# MVFD_I2C_Backpack.net
KiCad netlist of a schematic drawn in EAGLE
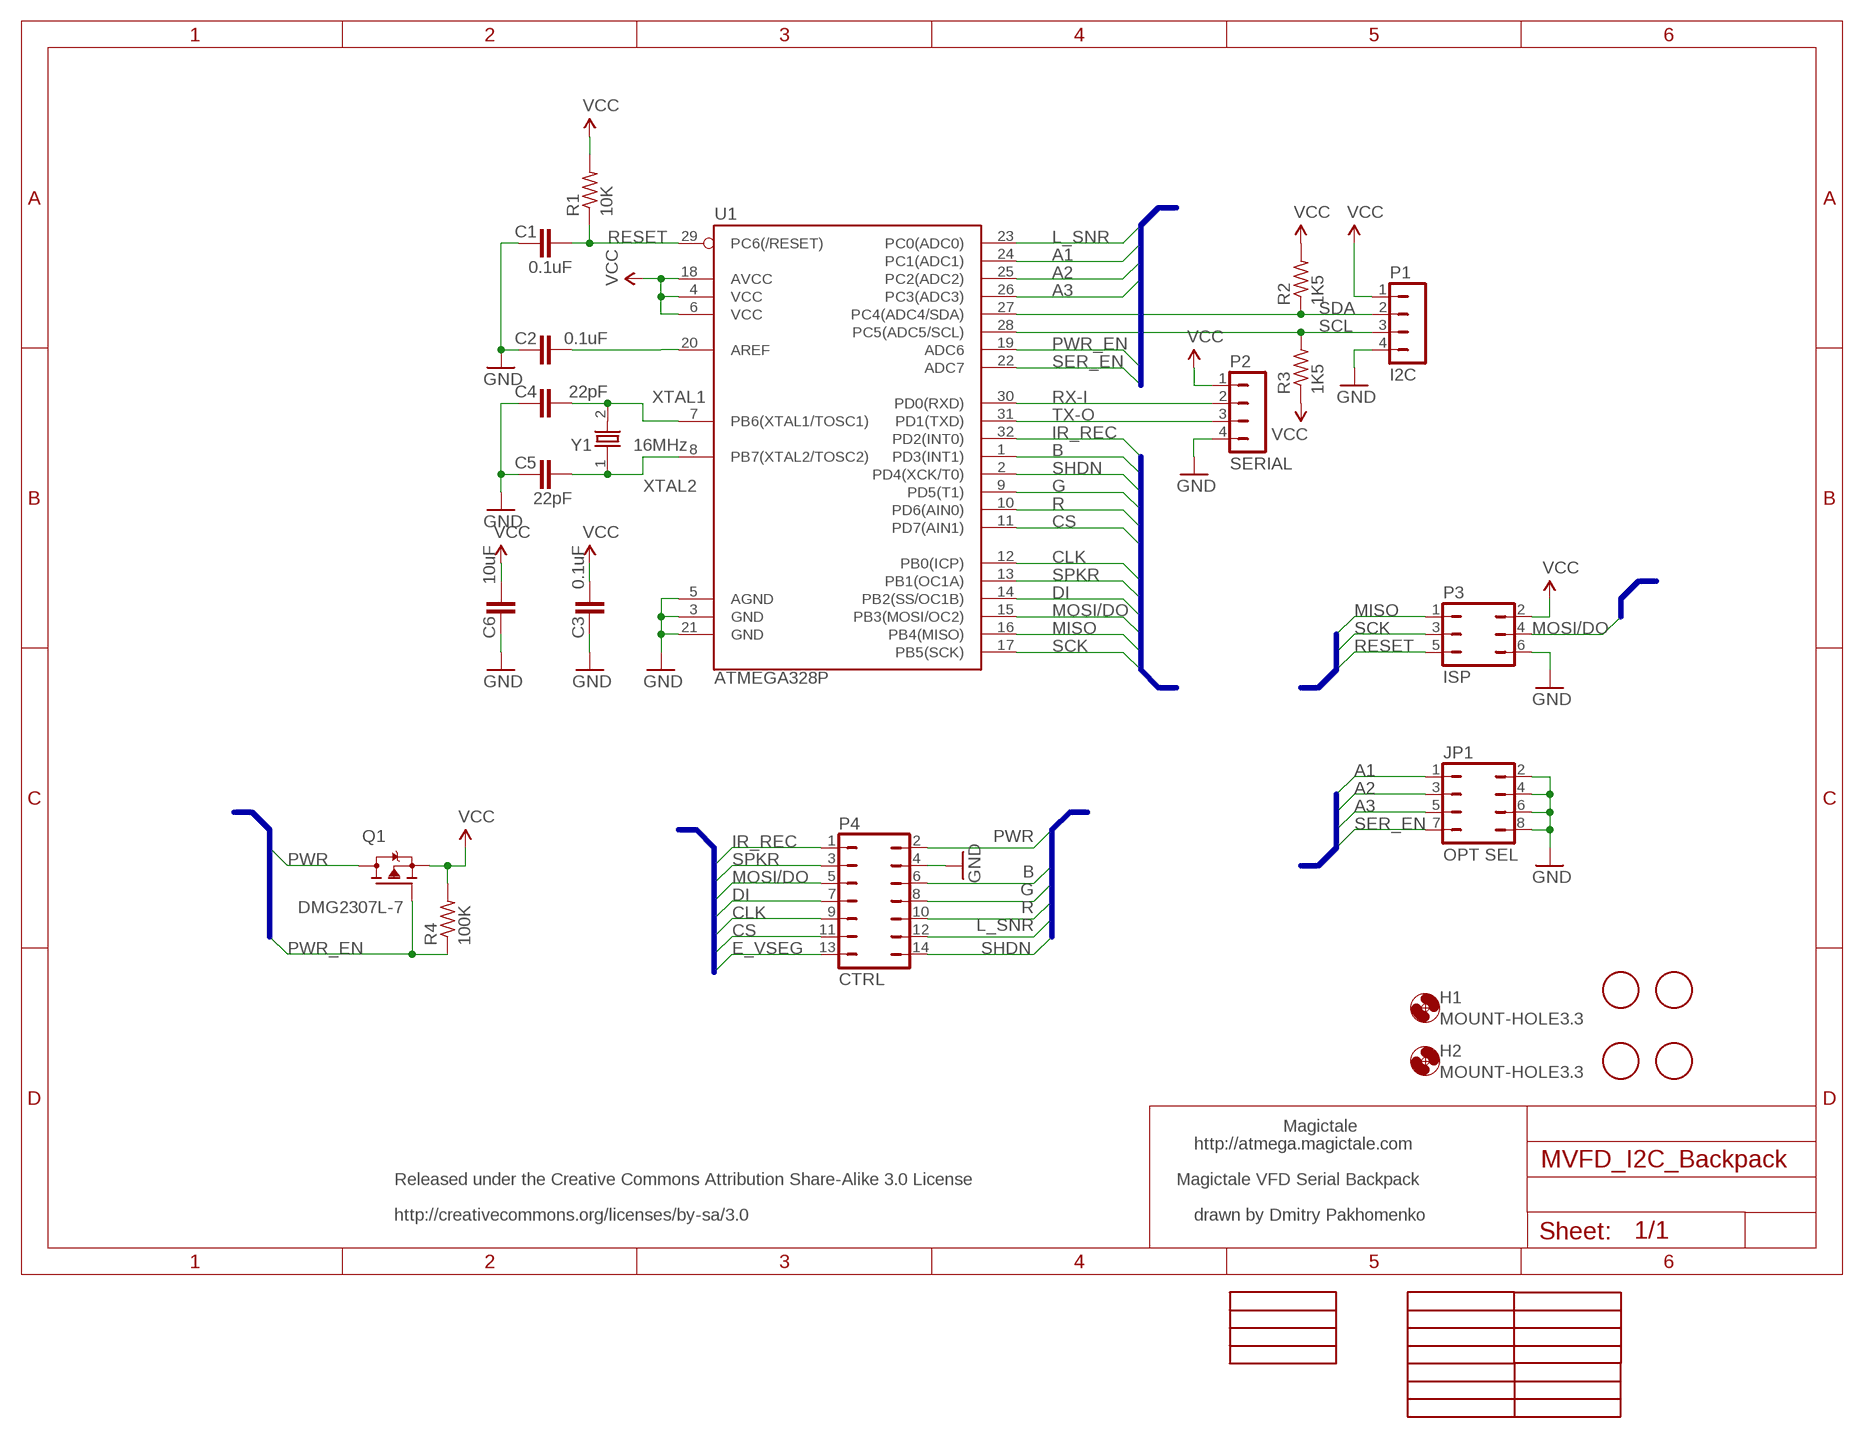
[diagram p0: schematic, sheet 1]

(export (version "E")
  (design (tool "Eeschema 10.0.6"))
  (components
    (comp (ref "C1")
      (value "0.1uF")
      (footprint "eagle-import:C1206")
      (libsource (lib "eagle-import") (part "CAPACITOR_NPOL-1206"))
    )
    (comp (ref "C2")
      (value "0.1uF")
      (footprint "eagle-import:C1206")
      (libsource (lib "eagle-import") (part "CAPACITOR_NPOL-1206"))
    )
    (comp (ref "C3")
      (value "0.1uF")
      (footprint "eagle-import:C1206")
      (libsource (lib "eagle-import") (part "CAPACITOR_NPOL-1206"))
    )
    (comp (ref "C4")
      (value "22pF")
      (footprint "eagle-import:C1206")
      (libsource (lib "eagle-import") (part "CAPACITOR_NPOL-1206"))
    )
    (comp (ref "C5")
      (value "22pF")
      (footprint "eagle-import:C1206")
      (libsource (lib "eagle-import") (part "CAPACITOR_NPOL-1206"))
    )
    (comp (ref "C6")
      (value "10uF")
      (footprint "eagle-import:C1206")
      (libsource (lib "eagle-import") (part "CAPACITOR_NPOL-1206"))
    )
    (comp (ref "FIDUTIAL1")
      (value "FIDUCIAL")
      (footprint "eagle-import:FIDUCIAL_1MM")
      (libsource (lib "eagle-import") (part "FIDUCIAL"))
    )
    (comp (ref "FIDUTIAL2")
      (value "FIDUCIAL")
      (footprint "eagle-import:FIDUCIAL_1MM")
      (libsource (lib "eagle-import") (part "FIDUCIAL"))
    )
    (comp (ref "FIDUTIAL3")
      (value "FIDUCIAL")
      (footprint "eagle-import:FIDUCIAL_1MM")
      (libsource (lib "eagle-import") (part "FIDUCIAL"))
    )
    (comp (ref "FIDUTIAL4")
      (value "FIDUCIAL")
      (footprint "eagle-import:FIDUCIAL_1MM")
      (libsource (lib "eagle-import") (part "FIDUCIAL"))
    )
    (comp (ref "H1")
      (value "MOUNT-HOLE3.3")
      (footprint "eagle-import:3,3")
      (libsource (lib "eagle-import") (part "MOUNT-HOLE3.3"))
    )
    (comp (ref "H2")
      (value "MOUNT-HOLE3.3")
      (footprint "eagle-import:3,3")
      (libsource (lib "eagle-import") (part "MOUNT-HOLE3.3"))
    )
    (comp (ref "JP1")
      (value "OPT SEL")
      (footprint "eagle-import:CONN_HEADER_2X04")
      (libsource (lib "eagle-import") (part "CONN_HEADER_2X04"))
    )
    (comp (ref "P1")
      (value "I2C")
      (footprint "eagle-import:CONN_HEADER_1X04_RA_POLAR")
      (libsource (lib "eagle-import") (part "CONN_HEADER_1X04RA_POLAR"))
    )
    (comp (ref "P2")
      (value "SERIAL")
      (footprint "eagle-import:CONN_HEADER_1X04_RA_POLAR")
      (libsource (lib "eagle-import") (part "CONN_HEADER_1X04RA_POLAR"))
    )
    (comp (ref "P3")
      (value "ISP")
      (footprint "eagle-import:CONN_HEADER_2X03")
      (libsource (lib "eagle-import") (part "CONN_HEADER_2X03"))
    )
    (comp (ref "P4")
      (value "CTRL")
      (footprint "eagle-import:CONN_HEADER_2X07_F_MIRR")
      (libsource (lib "eagle-import") (part "CONN_HEADER_2X07F_MIRR"))
    )
    (comp (ref "Q1")
      (value "DMG2307L-7")
      (footprint "eagle-import:SOT-23")
      (libsource (lib "eagle-import") (part "TRANSISTOR_FET_TSM2301CX"))
    )
    (comp (ref "R1")
      (value "10K")
      (footprint "eagle-import:R1206")
      (libsource (lib "eagle-import") (part "RESISTOR-1206"))
    )
    (comp (ref "R2")
      (value "1K5")
      (footprint "eagle-import:R1206")
      (libsource (lib "eagle-import") (part "RESISTOR-1206"))
    )
    (comp (ref "R3")
      (value "1K5")
      (footprint "eagle-import:R1206")
      (libsource (lib "eagle-import") (part "RESISTOR-1206"))
    )
    (comp (ref "R4")
      (value "100K")
      (footprint "eagle-import:R1206")
      (libsource (lib "eagle-import") (part "RESISTOR-1206"))
    )
    (comp (ref "U$1")
      (value "MT_LOGO")
      (footprint "eagle-import:MT_LOGO")
      (libsource (lib "eagle-import") (part "MT_LOGO"))
    )
    (comp (ref "U$2")
      (value "HDR_7P2R_DESCR")
      (footprint "eagle-import:HDR_7P2R_DESCR")
      (libsource (lib "eagle-import") (part "HDR_7P2R_DESCR"))
    )
    (comp (ref "U$4")
      (value "JUMP_4X2_DESCR")
      (footprint "eagle-import:JUMP_4X2_DESCR")
      (libsource (lib "eagle-import") (part "JUMP_4X2_DESCR"))
    )
    (comp (ref "U1")
      (value "ATMEGA328P")
      (footprint "eagle-import:TQFP32-08")
      (libsource (lib "eagle-import") (part "ATMEGA168"))
    )
    (comp (ref "Y1")
      (value "16MHz")
      (footprint "eagle-import:HC-49U")
      (libsource (lib "eagle-import") (part "OSC-XTAL-HC-49U-SMD"))
    )
  )
  (nets
    (net (code "1") (name "/A1") (class "Default")
      (node (ref "JP1") (pin "1") (pinfunction "1_1") (pintype "passive"))
      (node (ref "U1") (pin "24") (pinfunction "PC1(ADC1)_24") (pintype "bidirectional"))
    )
    (net (code "2") (name "/A2") (class "Default")
      (node (ref "JP1") (pin "3") (pinfunction "3_3") (pintype "passive"))
      (node (ref "U1") (pin "25") (pinfunction "PC2(ADC2)_25") (pintype "bidirectional"))
    )
    (net (code "3") (name "/A3") (class "Default")
      (node (ref "JP1") (pin "5") (pinfunction "5_5") (pintype "passive"))
      (node (ref "U1") (pin "26") (pinfunction "PC3(ADC3)_26") (pintype "bidirectional"))
    )
    (net (code "4") (name "/B") (class "Default")
      (node (ref "P4") (pin "6") (pinfunction "6_6") (pintype "passive"))
      (node (ref "U1") (pin "1") (pinfunction "PD3(INT1)_1") (pintype "bidirectional"))
    )
    (net (code "5") (name "/CLK") (class "Default")
      (node (ref "P4") (pin "9") (pinfunction "9_9") (pintype "passive"))
      (node (ref "U1") (pin "12") (pinfunction "PB0(ICP)_12") (pintype "bidirectional"))
    )
    (net (code "6") (name "/CS") (class "Default")
      (node (ref "P4") (pin "11") (pinfunction "11_11") (pintype "passive"))
      (node (ref "U1") (pin "11") (pinfunction "PD7(AIN1)_11") (pintype "bidirectional"))
    )
    (net (code "7") (name "/DI") (class "Default")
      (node (ref "P4") (pin "7") (pinfunction "7_7") (pintype "passive"))
      (node (ref "U1") (pin "14") (pinfunction "PB2(SS/OC1B)_14") (pintype "bidirectional"))
    )
    (net (code "8") (name "/E_VSEG") (class "Default")
      (node (ref "P4") (pin "13") (pinfunction "13_13") (pintype "passive"))
    )
    (net (code "9") (name "/G") (class "Default")
      (node (ref "P4") (pin "8") (pinfunction "8_8") (pintype "passive"))
      (node (ref "U1") (pin "9") (pinfunction "PD5(T1)_9") (pintype "bidirectional"))
    )
    (net (code "10") (name "/IR_REC") (class "Default")
      (node (ref "P4") (pin "1") (pinfunction "1_1") (pintype "passive"))
      (node (ref "U1") (pin "32") (pinfunction "PD2(INT0)_32") (pintype "bidirectional"))
    )
    (net (code "11") (name "/L_SNR") (class "Default")
      (node (ref "P4") (pin "12") (pinfunction "12_12") (pintype "passive"))
      (node (ref "U1") (pin "23") (pinfunction "PC0(ADC0)_23") (pintype "bidirectional"))
    )
    (net (code "12") (name "/MISO") (class "Default")
      (node (ref "P3") (pin "1") (pinfunction "1_1") (pintype "passive"))
      (node (ref "U1") (pin "16") (pinfunction "PB4(MISO)_16") (pintype "bidirectional"))
    )
    (net (code "13") (name "/MOSI{slash}DO") (class "Default")
      (node (ref "P3") (pin "4") (pinfunction "4_4") (pintype "passive"))
      (node (ref "P4") (pin "5") (pinfunction "5_5") (pintype "passive"))
      (node (ref "U1") (pin "15") (pinfunction "PB3(MOSI/OC2)_15") (pintype "bidirectional"))
    )
    (net (code "14") (name "/PWR") (class "Default")
      (node (ref "P4") (pin "2") (pinfunction "2_2") (pintype "passive"))
      (node (ref "Q1") (pin "3") (pinfunction "D_3") (pintype "passive"))
    )
    (net (code "15") (name "/PWR_EN") (class "Default")
      (node (ref "Q1") (pin "1") (pinfunction "G_1") (pintype "passive"))
      (node (ref "R4") (pin "1") (pinfunction "1_1") (pintype "passive"))
      (node (ref "U1") (pin "19") (pinfunction "ADC6_19") (pintype "bidirectional"))
    )
    (net (code "16") (name "/R") (class "Default")
      (node (ref "P4") (pin "10") (pinfunction "10_10") (pintype "passive"))
      (node (ref "U1") (pin "10") (pinfunction "PD6(AIN0)_10") (pintype "bidirectional"))
    )
    (net (code "17") (name "/RESET") (class "Default")
      (node (ref "C1") (pin "2") (pinfunction "2_2") (pintype "passive"))
      (node (ref "P3") (pin "5") (pinfunction "5_5") (pintype "passive"))
      (node (ref "R1") (pin "1") (pinfunction "1_1") (pintype "passive"))
      (node (ref "U1") (pin "29") (pinfunction "PC6(/RESET)_29") (pintype "bidirectional"))
    )
    (net (code "18") (name "/RX-I") (class "Default")
      (node (ref "P2") (pin "2") (pinfunction "2_2") (pintype "passive"))
      (node (ref "U1") (pin "30") (pinfunction "PD0(RXD)_30") (pintype "bidirectional"))
    )
    (net (code "19") (name "/SCK") (class "Default")
      (node (ref "P3") (pin "3") (pinfunction "3_3") (pintype "passive"))
      (node (ref "U1") (pin "17") (pinfunction "PB5(SCK)_17") (pintype "bidirectional"))
    )
    (net (code "20") (name "/SCL") (class "Default")
      (node (ref "P1") (pin "3") (pinfunction "3_3") (pintype "passive"))
      (node (ref "R3") (pin "2") (pinfunction "2_2") (pintype "passive"))
      (node (ref "U1") (pin "28") (pinfunction "PC5(ADC5/SCL)_28") (pintype "bidirectional"))
    )
    (net (code "21") (name "/SDA") (class "Default")
      (node (ref "P1") (pin "2") (pinfunction "2_2") (pintype "passive"))
      (node (ref "R2") (pin "1") (pinfunction "1_1") (pintype "passive"))
      (node (ref "U1") (pin "27") (pinfunction "PC4(ADC4/SDA)_27") (pintype "bidirectional"))
    )
    (net (code "22") (name "/SER_EN") (class "Default")
      (node (ref "JP1") (pin "7") (pinfunction "7_7") (pintype "passive"))
      (node (ref "U1") (pin "22") (pinfunction "ADC7_22") (pintype "bidirectional"))
    )
    (net (code "23") (name "/SHDN") (class "Default")
      (node (ref "P4") (pin "14") (pinfunction "14_14") (pintype "passive"))
      (node (ref "U1") (pin "2") (pinfunction "PD4(XCK/T0)_2") (pintype "bidirectional"))
    )
    (net (code "24") (name "/SPKR") (class "Default")
      (node (ref "P4") (pin "3") (pinfunction "3_3") (pintype "passive"))
      (node (ref "U1") (pin "13") (pinfunction "PB1(OC1A)_13") (pintype "bidirectional"))
    )
    (net (code "25") (name "/TX-O") (class "Default")
      (node (ref "P2") (pin "3") (pinfunction "3_3") (pintype "passive"))
      (node (ref "U1") (pin "31") (pinfunction "PD1(TXD)_31") (pintype "bidirectional"))
    )
    (net (code "26") (name "/XTAL1") (class "Default")
      (node (ref "C4") (pin "2") (pinfunction "2_2") (pintype "passive"))
      (node (ref "U1") (pin "7") (pinfunction "PB6(XTAL1/TOSC1)_7") (pintype "bidirectional"))
      (node (ref "Y1") (pin "2") (pinfunction "2_2") (pintype "passive"))
    )
    (net (code "27") (name "/XTAL2") (class "Default")
      (node (ref "C5") (pin "2") (pinfunction "2_2") (pintype "passive"))
      (node (ref "U1") (pin "8") (pinfunction "PB7(XTAL2/TOSC2)_8") (pintype "bidirectional"))
      (node (ref "Y1") (pin "1") (pinfunction "1_1") (pintype "passive"))
    )
    (net (code "28") (name "GND") (class "Default")
      (node (ref "C1") (pin "1") (pinfunction "1_1") (pintype "passive"))
      (node (ref "C2") (pin "1") (pinfunction "1_1") (pintype "passive"))
      (node (ref "C3") (pin "1") (pinfunction "1_1") (pintype "passive"))
      (node (ref "C4") (pin "1") (pinfunction "1_1") (pintype "passive"))
      (node (ref "C5") (pin "1") (pinfunction "1_1") (pintype "passive"))
      (node (ref "C6") (pin "1") (pinfunction "1_1") (pintype "passive"))
      (node (ref "JP1") (pin "2") (pinfunction "2_2") (pintype "passive"))
      (node (ref "JP1") (pin "4") (pinfunction "4_4") (pintype "passive"))
      (node (ref "JP1") (pin "6") (pinfunction "6_6") (pintype "passive"))
      (node (ref "JP1") (pin "8") (pinfunction "8_8") (pintype "passive"))
      (node (ref "P1") (pin "4") (pinfunction "4_4") (pintype "passive"))
      (node (ref "P2") (pin "4") (pinfunction "4_4") (pintype "passive"))
      (node (ref "P3") (pin "6") (pinfunction "6_6") (pintype "passive"))
      (node (ref "P4") (pin "4") (pinfunction "4_4") (pintype "passive"))
      (node (ref "U1") (pin "21") (pinfunction "GND_21") (pintype "bidirectional"))
      (node (ref "U1") (pin "3") (pinfunction "GND_3") (pintype "bidirectional"))
      (node (ref "U1") (pin "5") (pinfunction "AGND_5") (pintype "bidirectional"))
    )
    (net (code "29") (name "Net-(U1-AREF)") (class "Default")
      (node (ref "C2") (pin "2") (pinfunction "2_2") (pintype "passive"))
      (node (ref "U1") (pin "20") (pinfunction "AREF_20") (pintype "bidirectional"))
    )
    (net (code "30") (name "VCC") (class "Default")
      (node (ref "C3") (pin "2") (pinfunction "2_2") (pintype "passive"))
      (node (ref "C6") (pin "2") (pinfunction "2_2") (pintype "passive"))
      (node (ref "P1") (pin "1") (pinfunction "1_1") (pintype "passive"))
      (node (ref "P2") (pin "1") (pinfunction "1_1") (pintype "passive"))
      (node (ref "P3") (pin "2") (pinfunction "2_2") (pintype "passive"))
      (node (ref "Q1") (pin "2") (pinfunction "S_2") (pintype "passive"))
      (node (ref "R1") (pin "2") (pinfunction "2_2") (pintype "passive"))
      (node (ref "R2") (pin "2") (pinfunction "2_2") (pintype "passive"))
      (node (ref "R3") (pin "1") (pinfunction "1_1") (pintype "passive"))
      (node (ref "R4") (pin "2") (pinfunction "2_2") (pintype "passive"))
      (node (ref "U1") (pin "18") (pinfunction "AVCC_18") (pintype "bidirectional"))
      (node (ref "U1") (pin "4") (pinfunction "VCC_4") (pintype "bidirectional"))
      (node (ref "U1") (pin "6") (pinfunction "VCC_6") (pintype "bidirectional"))
    )
  )
)
